# ddrive-esp-deadrail-1-4.net
KiCad netlist of a schematic drawn in EAGLE
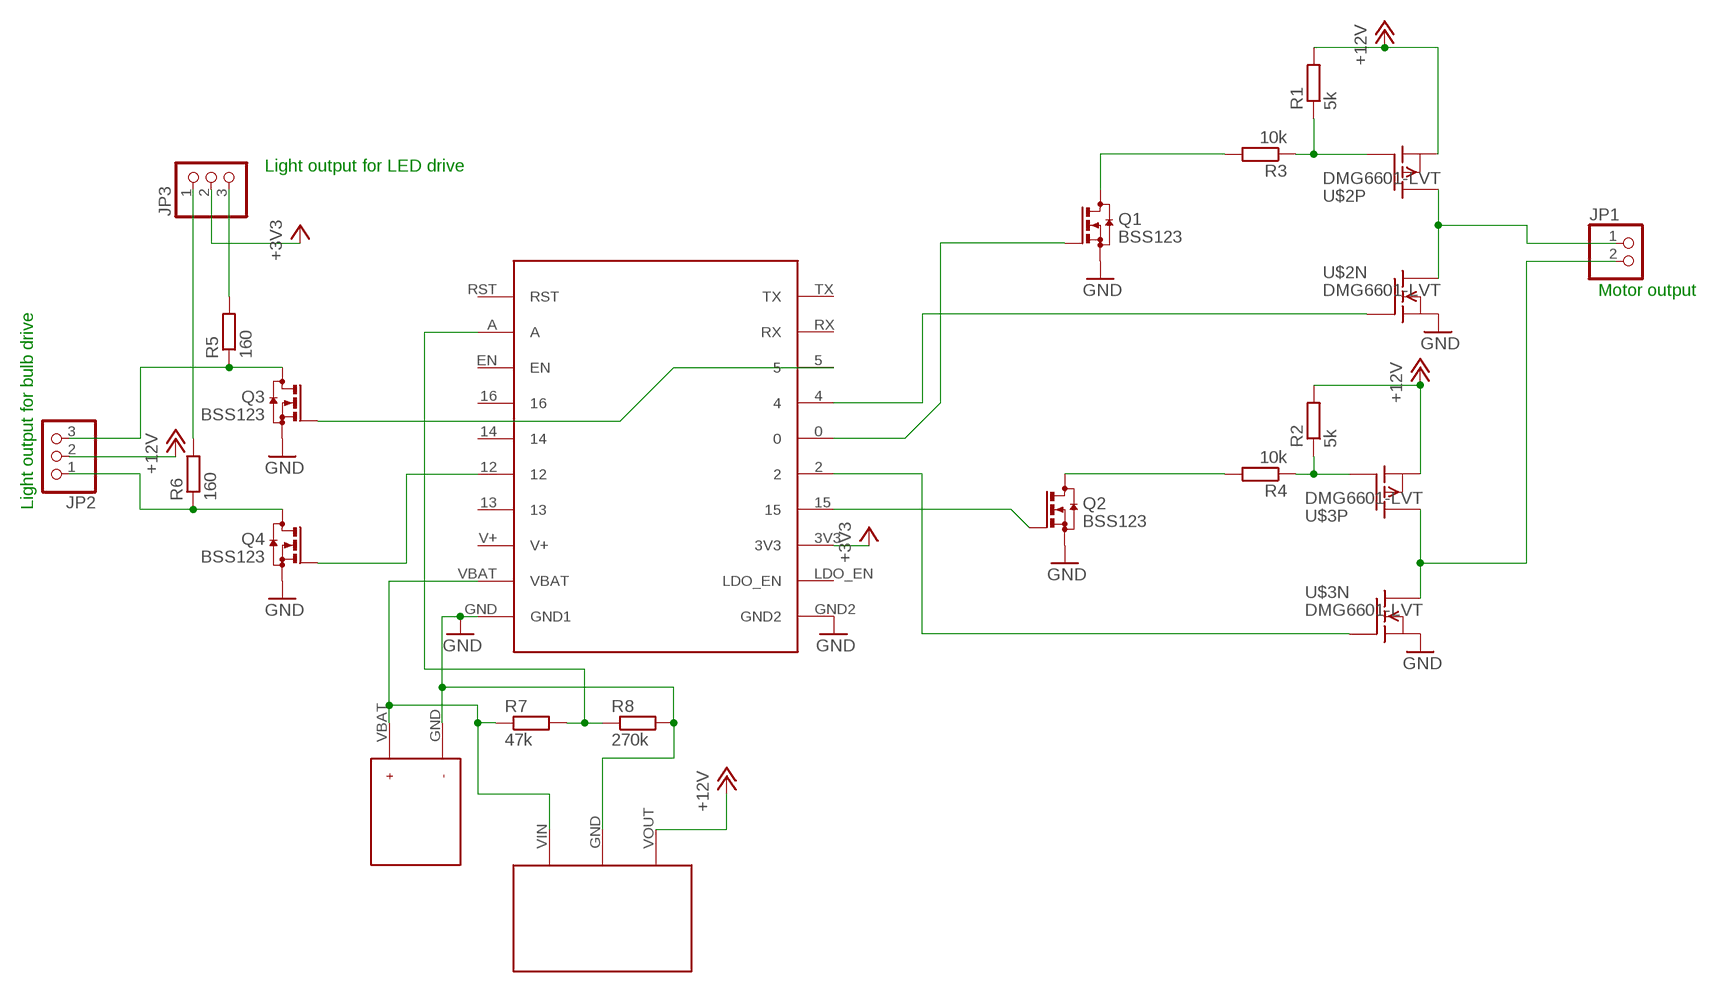
[diagram p0: schematic, sheet 1]

(export (version "E")
  (design (tool "Eeschema 10.0.6"))
  (components
    (comp (ref "JP1")
      (value "PINHD-1X2")
      (footprint "eagle-import:1X02")
      (libsource (lib "eagle-import") (part "PINHD-1X2"))
    )
    (comp (ref "JP2")
      (value "PINHD-1X3")
      (footprint "eagle-import:1X03")
      (libsource (lib "eagle-import") (part "PINHD-1X3"))
    )
    (comp (ref "JP3")
      (value "PINHD-1X3")
      (footprint "eagle-import:1X03")
      (libsource (lib "eagle-import") (part "PINHD-1X3"))
    )
    (comp (ref "Q1")
      (value "BSS123")
      (footprint "eagle-import:SOT23")
      (libsource (lib "eagle-import") (part "BSS123"))
    )
    (comp (ref "Q2")
      (value "BSS123")
      (footprint "eagle-import:SOT23")
      (libsource (lib "eagle-import") (part "BSS123"))
    )
    (comp (ref "Q3")
      (value "BSS123")
      (footprint "eagle-import:SOT23")
      (libsource (lib "eagle-import") (part "BSS123"))
    )
    (comp (ref "Q4")
      (value "BSS123")
      (footprint "eagle-import:SOT23")
      (libsource (lib "eagle-import") (part "BSS123"))
    )
    (comp (ref "R1")
      (value "5k")
      (footprint "eagle-import:R0805")
      (libsource (lib "eagle-import") (part "R-EU_R0805"))
    )
    (comp (ref "R2")
      (value "5k")
      (footprint "eagle-import:R0805")
      (libsource (lib "eagle-import") (part "R-EU_R0805"))
    )
    (comp (ref "R3")
      (value "10k")
      (footprint "eagle-import:R0805")
      (libsource (lib "eagle-import") (part "R-EU_R0805"))
    )
    (comp (ref "R4")
      (value "10k")
      (footprint "eagle-import:R0805")
      (libsource (lib "eagle-import") (part "R-EU_R0805"))
    )
    (comp (ref "R5")
      (value "160")
      (footprint "eagle-import:R0805")
      (libsource (lib "eagle-import") (part "R-EU_R0805"))
    )
    (comp (ref "R6")
      (value "160")
      (footprint "eagle-import:R0805")
      (libsource (lib "eagle-import") (part "R-EU_R0805"))
    )
    (comp (ref "R7")
      (value "47k")
      (footprint "eagle-import:R0805")
      (libsource (lib "eagle-import") (part "R-EU_R0805"))
    )
    (comp (ref "R8")
      (value "270k")
      (footprint "eagle-import:R0805")
      (libsource (lib "eagle-import") (part "R-EU_R0805"))
    )
    (comp (ref "U$1")
      (value "ESP12-HUZZAH")
      (footprint "eagle-import:ESP12-HUZZAH")
      (libsource (lib "eagle-import") (part "ESP12-HUZZAH"))
    )
    (comp (ref "U$2")
      (value "DMG6601-LVT")
      (footprint "eagle-import:TSOT-26")
      (libsource (lib "eagle-import") (part "DMG6601-LVT"))
    )
    (comp (ref "U$3")
      (value "DMG6601-LVT")
      (footprint "eagle-import:TSOT-26")
      (libsource (lib "eagle-import") (part "DMG6601-LVT"))
    )
    (comp (ref "U$4")
      (value "JST-PINHD")
      (footprint "eagle-import:JST-PINHDR")
      (libsource (lib "eagle-import") (part "JST-PINHD"))
    )
    (comp (ref "U$5")
      (value "POLOLU-VREG12")
      (footprint "eagle-import:POLOLU-REGULATOR")
      (libsource (lib "eagle-import") (part "POLOLU-VREG12"))
    )
  )
  (nets
    (net (code "1") (name "+3V3") (class "Default")
      (node (ref "JP3") (pin "2") (pinfunction "2_2") (pintype "passive"))
      (node (ref "U$1") (pin "3V3") (pinfunction "3V3_3V3") (pintype "power_in"))
    )
    (net (code "2") (name "+12V") (class "Default")
      (node (ref "JP2") (pin "2") (pinfunction "2_2") (pintype "passive"))
      (node (ref "R1") (pin "2") (pinfunction "2_2") (pintype "passive"))
      (node (ref "R2") (pin "2") (pinfunction "2_2") (pintype "passive"))
      (node (ref "U$2") (pin "2") (pinfunction "S_2") (pintype "passive"))
      (node (ref "U$3") (pin "2") (pinfunction "S_2") (pintype "passive"))
      (node (ref "U$5") (pin "VOUT") (pinfunction "VOUT_VOUT") (pintype "bidirectional"))
    )
    (net (code "3") (name "/V+") (class "Default")
      (node (ref "U$1") (pin "V+") (pinfunction "V+_V+") (pintype "power_in"))
    )
    (net (code "4") (name "GND") (class "Default")
      (node (ref "Q1") (pin "2") (pinfunction "S_2") (pintype "passive"))
      (node (ref "Q2") (pin "2") (pinfunction "S_2") (pintype "passive"))
      (node (ref "Q3") (pin "2") (pinfunction "S_2") (pintype "passive"))
      (node (ref "Q4") (pin "2") (pinfunction "S_2") (pintype "passive"))
      (node (ref "R8") (pin "2") (pinfunction "2_2") (pintype "passive"))
      (node (ref "U$1") (pin "GND") (pinfunction "GND1_GND") (pintype "power_in"))
      (node (ref "U$1") (pin "GND2") (pinfunction "GND2_GND2") (pintype "power_in"))
      (node (ref "U$2") (pin "5") (pinfunction "S_5") (pintype "passive"))
      (node (ref "U$3") (pin "5") (pinfunction "S_5") (pintype "passive"))
      (node (ref "U$4") (pin "GND") (pinfunction "P$1_GND") (pintype "power_in"))
      (node (ref "U$5") (pin "GND") (pinfunction "GND_GND") (pintype "bidirectional"))
    )
    (net (code "5") (name "Net-(JP3-Pad1)") (class "Default")
      (node (ref "JP3") (pin "1") (pinfunction "1_1") (pintype "passive"))
      (node (ref "R6") (pin "2") (pinfunction "2_2") (pintype "passive"))
    )
    (net (code "6") (name "Net-(JP3-Pad3)") (class "Default")
      (node (ref "JP3") (pin "3") (pinfunction "3_3") (pintype "passive"))
      (node (ref "R5") (pin "2") (pinfunction "2_2") (pintype "passive"))
    )
    (net (code "7") (name "Net-(Q1-D)") (class "Default")
      (node (ref "Q1") (pin "3") (pinfunction "D_3") (pintype "passive"))
      (node (ref "R3") (pin "2") (pinfunction "2_2") (pintype "passive"))
    )
    (net (code "8") (name "Net-(Q1-G)") (class "Default")
      (node (ref "Q1") (pin "1") (pinfunction "G_1") (pintype "passive"))
      (node (ref "U$1") (pin "0") (pinfunction "0_0") (pintype "bidirectional"))
    )
    (net (code "9") (name "Net-(Q2-D)") (class "Default")
      (node (ref "Q2") (pin "3") (pinfunction "D_3") (pintype "passive"))
      (node (ref "R4") (pin "2") (pinfunction "2_2") (pintype "passive"))
    )
    (net (code "10") (name "Net-(Q2-G)") (class "Default")
      (node (ref "Q2") (pin "1") (pinfunction "G_1") (pintype "passive"))
      (node (ref "U$1") (pin "15") (pinfunction "15_15") (pintype "bidirectional"))
    )
    (net (code "11") (name "Net-(Q3-D)") (class "Default")
      (node (ref "JP2") (pin "3") (pinfunction "3_3") (pintype "passive"))
      (node (ref "Q3") (pin "3") (pinfunction "D_3") (pintype "passive"))
      (node (ref "R5") (pin "1") (pinfunction "1_1") (pintype "passive"))
    )
    (net (code "12") (name "Net-(Q3-G)") (class "Default")
      (node (ref "Q3") (pin "1") (pinfunction "G_1") (pintype "passive"))
      (node (ref "U$1") (pin "5") (pinfunction "5_5") (pintype "bidirectional"))
    )
    (net (code "13") (name "Net-(Q4-D)") (class "Default")
      (node (ref "JP2") (pin "1") (pinfunction "1_1") (pintype "passive"))
      (node (ref "Q4") (pin "3") (pinfunction "D_3") (pintype "passive"))
      (node (ref "R6") (pin "1") (pinfunction "1_1") (pintype "passive"))
    )
    (net (code "14") (name "Net-(Q4-G)") (class "Default")
      (node (ref "Q4") (pin "1") (pinfunction "G_1") (pintype "passive"))
      (node (ref "U$1") (pin "12") (pinfunction "12_12") (pintype "bidirectional"))
    )
    (net (code "15") (name "Net-(R7-Pad2)") (class "Default")
      (node (ref "R7") (pin "2") (pinfunction "2_2") (pintype "passive"))
      (node (ref "R8") (pin "1") (pinfunction "1_1") (pintype "passive"))
      (node (ref "U$1") (pin "A") (pinfunction "A_A") (pintype "bidirectional"))
    )
    (net (code "16") (name "Net-(U$2A-D)") (class "Default")
      (node (ref "JP1") (pin "1") (pinfunction "1_1") (pintype "passive"))
      (node (ref "U$2") (pin "4") (pinfunction "D_4") (pintype "passive"))
      (node (ref "U$2") (pin "6") (pinfunction "D_6") (pintype "passive"))
    )
    (net (code "17") (name "Net-(U$2A-G)") (class "Default")
      (node (ref "U$1") (pin "4") (pinfunction "4_4") (pintype "bidirectional"))
      (node (ref "U$2") (pin "1") (pinfunction "G_1") (pintype "passive"))
    )
    (net (code "18") (name "Net-(U$2B-G)") (class "Default")
      (node (ref "R1") (pin "1") (pinfunction "1_1") (pintype "passive"))
      (node (ref "R3") (pin "1") (pinfunction "1_1") (pintype "passive"))
      (node (ref "U$2") (pin "3") (pinfunction "G_3") (pintype "passive"))
    )
    (net (code "19") (name "Net-(U$3A-D)") (class "Default")
      (node (ref "JP1") (pin "2") (pinfunction "2_2") (pintype "passive"))
      (node (ref "U$3") (pin "4") (pinfunction "D_4") (pintype "passive"))
      (node (ref "U$3") (pin "6") (pinfunction "D_6") (pintype "passive"))
    )
    (net (code "20") (name "Net-(U$3A-G)") (class "Default")
      (node (ref "U$1") (pin "2") (pinfunction "2_2") (pintype "bidirectional"))
      (node (ref "U$3") (pin "1") (pinfunction "G_1") (pintype "passive"))
    )
    (net (code "21") (name "Net-(U$3B-G)") (class "Default")
      (node (ref "R2") (pin "1") (pinfunction "1_1") (pintype "passive"))
      (node (ref "R4") (pin "1") (pinfunction "1_1") (pintype "passive"))
      (node (ref "U$3") (pin "3") (pinfunction "G_3") (pintype "passive"))
    )
    (net (code "22") (name "Net-(U$4-P$2)") (class "Default")
      (node (ref "R7") (pin "1") (pinfunction "1_1") (pintype "passive"))
      (node (ref "U$1") (pin "VBAT") (pinfunction "VBAT_VBAT") (pintype "power_in"))
      (node (ref "U$4") (pin "VBAT") (pinfunction "P$2_VBAT") (pintype "power_in"))
      (node (ref "U$5") (pin "VIN") (pinfunction "VIN_VIN") (pintype "bidirectional"))
    )
    (net (code "23") (name "unconnected-(U$1-Pad13)") (class "Default")
      (node (ref "U$1") (pin "13") (pinfunction "13_13") (pintype "bidirectional"))
    )
    (net (code "24") (name "unconnected-(U$1-Pad14)") (class "Default")
      (node (ref "U$1") (pin "14") (pinfunction "14_14") (pintype "bidirectional"))
    )
    (net (code "25") (name "unconnected-(U$1-Pad16)") (class "Default")
      (node (ref "U$1") (pin "16") (pinfunction "16_16") (pintype "bidirectional"))
    )
    (net (code "26") (name "unconnected-(U$1-PadEN)") (class "Default")
      (node (ref "U$1") (pin "EN") (pinfunction "EN_EN") (pintype "bidirectional"))
    )
    (net (code "27") (name "unconnected-(U$1-PadLDO_EN)") (class "Default")
      (node (ref "U$1") (pin "LDO_EN") (pinfunction "LDO_EN_LDO_EN") (pintype "bidirectional"))
    )
    (net (code "28") (name "unconnected-(U$1-PadRST)") (class "Default")
      (node (ref "U$1") (pin "RST") (pinfunction "RST_RST") (pintype "bidirectional"))
    )
    (net (code "29") (name "unconnected-(U$1-PadRX)") (class "Default")
      (node (ref "U$1") (pin "RX") (pinfunction "RX_RX") (pintype "bidirectional"))
    )
    (net (code "30") (name "unconnected-(U$1-PadTX)") (class "Default")
      (node (ref "U$1") (pin "TX") (pinfunction "TX_TX") (pintype "bidirectional"))
    )
  )
)
